# Server.net
KiCad netlist of a schematic drawn in EAGLE
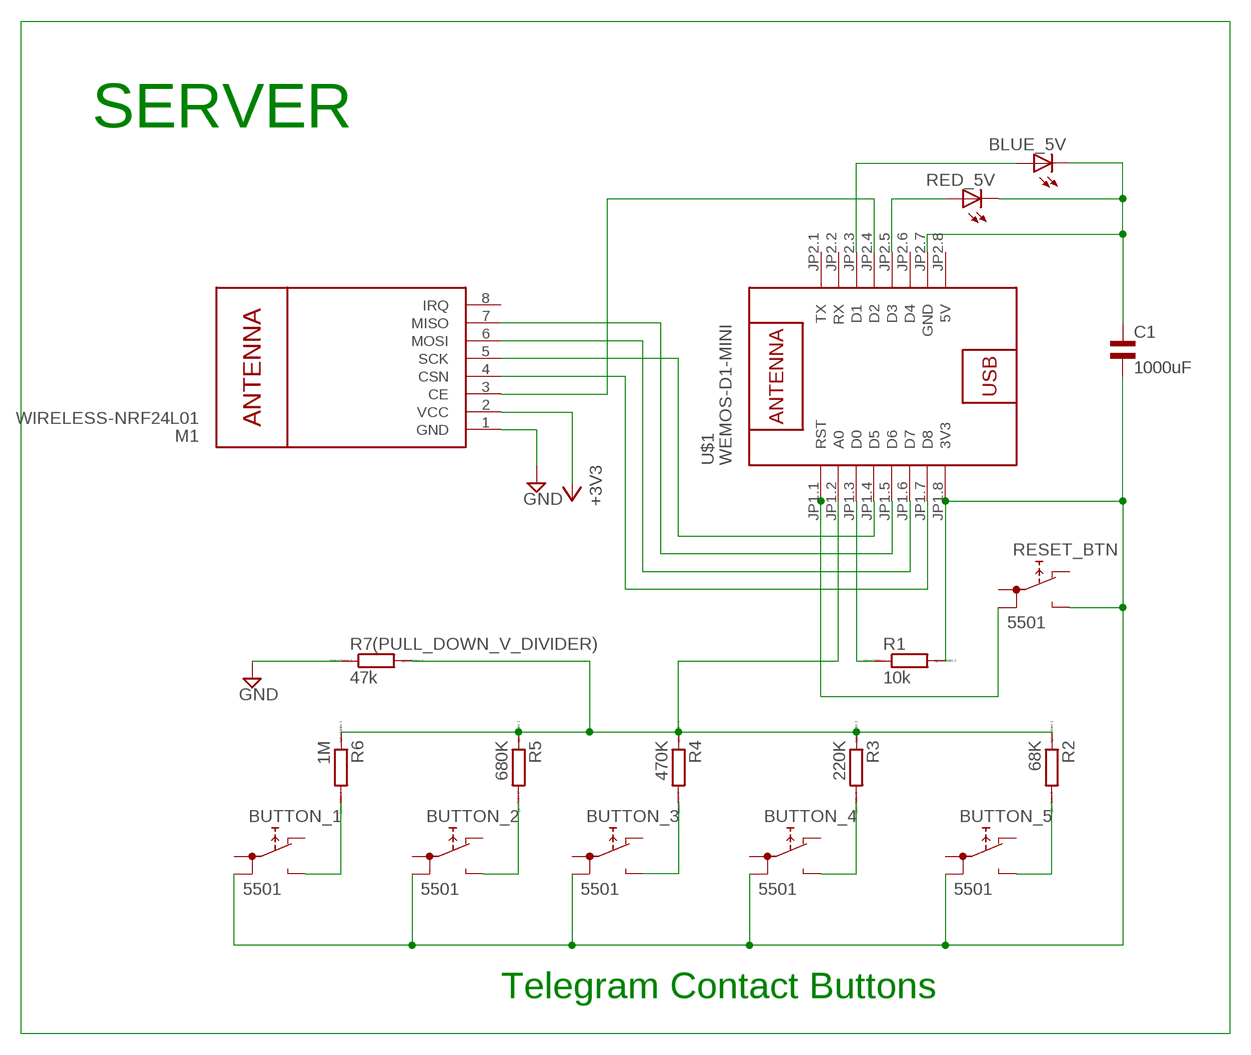
[diagram p0: schematic, sheet 1]

(export (version "E")
  (design (tool "Eeschema 10.0.6"))
  (components
    (comp (ref "BLUE_5V")
      (value "LED5MM")
      (footprint "eagle-import:LED5MM")
      (libsource (lib "eagle-import") (part "LED5MM"))
    )
    (comp (ref "BUTTON_1")
      (value "5501")
      (footprint "eagle-import:5501")
      (libsource (lib "eagle-import") (part "55?01"))
    )
    (comp (ref "BUTTON_2")
      (value "5501")
      (footprint "eagle-import:5501")
      (libsource (lib "eagle-import") (part "55?01"))
    )
    (comp (ref "BUTTON_3")
      (value "5501")
      (footprint "eagle-import:5501")
      (libsource (lib "eagle-import") (part "55?01"))
    )
    (comp (ref "BUTTON_4")
      (value "5501")
      (footprint "eagle-import:5501")
      (libsource (lib "eagle-import") (part "55?01"))
    )
    (comp (ref "BUTTON_5")
      (value "5501")
      (footprint "eagle-import:5501")
      (libsource (lib "eagle-import") (part "55?01"))
    )
    (comp (ref "C1")
      (value "1000uF")
      (footprint "eagle-import:EU35-12")
      (libsource (lib "eagle-import") (part "EL-BI35-12AXIAL"))
    )
    (comp (ref "M1")
      (value "WIRELESS-NRF24L01")
      (footprint "eagle-import:WIRELESS-NRF24L01")
      (libsource (lib "eagle-import") (part "WIRELESS-NRF24L01"))
    )
    (comp (ref "R1")
      (value "10k")
      (footprint "eagle-import:0207_10")
      (libsource (lib "eagle-import") (part "R0207/10"))
    )
    (comp (ref "R2")
      (value "68K")
      (footprint "eagle-import:0207_10")
      (libsource (lib "eagle-import") (part "R0207/10"))
    )
    (comp (ref "R3")
      (value "220K")
      (footprint "eagle-import:0207_10")
      (libsource (lib "eagle-import") (part "R0207/10"))
    )
    (comp (ref "R4")
      (value "470K")
      (footprint "eagle-import:0207_10")
      (libsource (lib "eagle-import") (part "R0207/10"))
    )
    (comp (ref "R5")
      (value "680K")
      (footprint "eagle-import:0207_10")
      (libsource (lib "eagle-import") (part "R0207/10"))
    )
    (comp (ref "R6")
      (value "1M")
      (footprint "eagle-import:0207_10")
      (libsource (lib "eagle-import") (part "R0207/10"))
    )
    (comp (ref "R7(PULL_DOWN_V_DIVIDER)")
      (value "47k")
      (footprint "eagle-import:0207_10")
      (libsource (lib "eagle-import") (part "R0207/10"))
    )
    (comp (ref "RED_5V")
      (value "LED5MM")
      (footprint "eagle-import:LED5MM")
      (libsource (lib "eagle-import") (part "LED5MM"))
    )
    (comp (ref "RESET_BTN")
      (value "5501")
      (footprint "eagle-import:5501")
      (libsource (lib "eagle-import") (part "55?01"))
    )
    (comp (ref "U$1")
      (value "WEMOS-D1-MINI")
      (footprint "eagle-import:WEMOS-D1-MINI")
      (libsource (lib "eagle-import") (part "WEMOS-D1-MINI"))
    )
  )
  (nets
    (net (code "1") (name "+3V3") (class "Default")
      (node (ref "M1") (pin "2") (pinfunction "VCC_2") (pintype "power_in"))
    )
    (net (code "2") (name "/5V") (class "Default")
      (node (ref "U$1") (pin "JP2.8") (pinfunction "5V_JP2.8") (pintype "power_in"))
    )
    (net (code "3") (name "GND") (class "Default")
      (node (ref "M1") (pin "1") (pinfunction "GND_1") (pintype "power_in"))
      (node (ref "R7(PULL_DOWN_V_DIVIDER)") (pin "1") (pinfunction "1_1") (pintype "passive"))
    )
    (net (code "4") (name "Net-(BLUE_5V-C)") (class "Default")
      (node (ref "BLUE_5V") (pin "K") (pinfunction "C_K") (pintype "passive"))
      (node (ref "C1") (pin "1") (pinfunction "1_1") (pintype "passive"))
      (node (ref "RED_5V") (pin "K") (pinfunction "C_K") (pintype "passive"))
      (node (ref "U$1") (pin "JP2.7") (pinfunction "GND_JP2.7") (pintype "power_in"))
    )
    (net (code "5") (name "Net-(BUTTON_1-PadNO)") (class "Default")
      (node (ref "BUTTON_1") (pin "NO") (pinfunction "NO_NO") (pintype "passive"))
      (node (ref "R6") (pin "2") (pinfunction "2_2") (pintype "passive"))
    )
    (net (code "6") (name "Net-(BUTTON_2-PadNO)") (class "Default")
      (node (ref "BUTTON_2") (pin "NO") (pinfunction "NO_NO") (pintype "passive"))
      (node (ref "R5") (pin "2") (pinfunction "2_2") (pintype "passive"))
    )
    (net (code "7") (name "Net-(BUTTON_3-PadNO)") (class "Default")
      (node (ref "BUTTON_3") (pin "NO") (pinfunction "NO_NO") (pintype "passive"))
      (node (ref "R4") (pin "2") (pinfunction "2_2") (pintype "passive"))
    )
    (net (code "8") (name "Net-(BUTTON_4-PadNO)") (class "Default")
      (node (ref "BUTTON_4") (pin "NO") (pinfunction "NO_NO") (pintype "passive"))
      (node (ref "R3") (pin "2") (pinfunction "2_2") (pintype "passive"))
    )
    (net (code "9") (name "Net-(BUTTON_5-PadNO)") (class "Default")
      (node (ref "BUTTON_5") (pin "NO") (pinfunction "NO_NO") (pintype "passive"))
      (node (ref "R2") (pin "2") (pinfunction "2_2") (pintype "passive"))
    )
    (net (code "10") (name "Net-(M1-CE)") (class "Default")
      (node (ref "M1") (pin "3") (pinfunction "CE_3") (pintype "bidirectional"))
      (node (ref "U$1") (pin "JP2.4") (pinfunction "D2_JP2.4") (pintype "bidirectional"))
    )
    (net (code "11") (name "Net-(M1-CSN)") (class "Default")
      (node (ref "M1") (pin "4") (pinfunction "CSN_4") (pintype "bidirectional"))
      (node (ref "U$1") (pin "JP1.7") (pinfunction "D8_JP1.7") (pintype "bidirectional"))
    )
    (net (code "12") (name "Net-(M1-MISO)") (class "Default")
      (node (ref "M1") (pin "7") (pinfunction "MISO_7") (pintype "bidirectional"))
      (node (ref "U$1") (pin "JP1.5") (pinfunction "D6_JP1.5") (pintype "bidirectional"))
    )
    (net (code "13") (name "Net-(M1-MOSI)") (class "Default")
      (node (ref "M1") (pin "6") (pinfunction "MOSI_6") (pintype "bidirectional"))
      (node (ref "U$1") (pin "JP1.6") (pinfunction "D7_JP1.6") (pintype "bidirectional"))
    )
    (net (code "14") (name "Net-(M1-SCK)") (class "Default")
      (node (ref "M1") (pin "5") (pinfunction "SCK_5") (pintype "bidirectional"))
      (node (ref "U$1") (pin "JP1.4") (pinfunction "D5_JP1.4") (pintype "bidirectional"))
    )
    (net (code "15") (name "Net-(U$1-3V3)") (class "Default")
      (node (ref "BUTTON_1") (pin "1B") (pinfunction "1B_1B") (pintype "passive"))
      (node (ref "BUTTON_2") (pin "1B") (pinfunction "1B_1B") (pintype "passive"))
      (node (ref "BUTTON_3") (pin "1B") (pinfunction "1B_1B") (pintype "passive"))
      (node (ref "BUTTON_4") (pin "1B") (pinfunction "1B_1B") (pintype "passive"))
      (node (ref "BUTTON_5") (pin "1B") (pinfunction "1B_1B") (pintype "passive"))
      (node (ref "C1") (pin "2") (pinfunction "2_2") (pintype "passive"))
      (node (ref "R1") (pin "2") (pinfunction "2_2") (pintype "passive"))
      (node (ref "RESET_BTN") (pin "NO") (pinfunction "NO_NO") (pintype "passive"))
      (node (ref "U$1") (pin "JP1.8") (pinfunction "3V3_JP1.8") (pintype "power_in"))
    )
    (net (code "16") (name "Net-(U$1-A0)") (class "Default")
      (node (ref "R2") (pin "1") (pinfunction "1_1") (pintype "passive"))
      (node (ref "R3") (pin "1") (pinfunction "1_1") (pintype "passive"))
      (node (ref "R4") (pin "1") (pinfunction "1_1") (pintype "passive"))
      (node (ref "R5") (pin "1") (pinfunction "1_1") (pintype "passive"))
      (node (ref "R6") (pin "1") (pinfunction "1_1") (pintype "passive"))
      (node (ref "R7(PULL_DOWN_V_DIVIDER)") (pin "2") (pinfunction "2_2") (pintype "passive"))
      (node (ref "U$1") (pin "JP1.2") (pinfunction "A0_JP1.2") (pintype "bidirectional"))
    )
    (net (code "17") (name "Net-(U$1-D0)") (class "Default")
      (node (ref "R1") (pin "1") (pinfunction "1_1") (pintype "passive"))
      (node (ref "U$1") (pin "JP1.3") (pinfunction "D0_JP1.3") (pintype "bidirectional"))
    )
    (net (code "18") (name "Net-(U$1-D1)") (class "Default")
      (node (ref "BLUE_5V") (pin "A") (pinfunction "A_A") (pintype "passive"))
      (node (ref "U$1") (pin "JP2.3") (pinfunction "D1_JP2.3") (pintype "bidirectional"))
    )
    (net (code "19") (name "Net-(U$1-D3)") (class "Default")
      (node (ref "RED_5V") (pin "A") (pinfunction "A_A") (pintype "passive"))
      (node (ref "U$1") (pin "JP2.5") (pinfunction "D3_JP2.5") (pintype "bidirectional"))
    )
    (net (code "20") (name "Net-(U$1-RST)") (class "Default")
      (node (ref "RESET_BTN") (pin "1B") (pinfunction "1B_1B") (pintype "passive"))
      (node (ref "U$1") (pin "JP1.1") (pinfunction "RST_JP1.1") (pintype "bidirectional"))
    )
    (net (code "21") (name "unconnected-(BUTTON_1-Pad1A)") (class "Default")
      (node (ref "BUTTON_1") (pin "1A") (pinfunction "1A_1A") (pintype "passive"))
    )
    (net (code "22") (name "unconnected-(BUTTON_1-PadNC)") (class "Default")
      (node (ref "BUTTON_1") (pin "NC") (pinfunction "NC_NC") (pintype "passive"))
    )
    (net (code "23") (name "unconnected-(BUTTON_2-Pad1A)") (class "Default")
      (node (ref "BUTTON_2") (pin "1A") (pinfunction "1A_1A") (pintype "passive"))
    )
    (net (code "24") (name "unconnected-(BUTTON_2-PadNC)") (class "Default")
      (node (ref "BUTTON_2") (pin "NC") (pinfunction "NC_NC") (pintype "passive"))
    )
    (net (code "25") (name "unconnected-(BUTTON_3-Pad1A)") (class "Default")
      (node (ref "BUTTON_3") (pin "1A") (pinfunction "1A_1A") (pintype "passive"))
    )
    (net (code "26") (name "unconnected-(BUTTON_3-PadNC)") (class "Default")
      (node (ref "BUTTON_3") (pin "NC") (pinfunction "NC_NC") (pintype "passive"))
    )
    (net (code "27") (name "unconnected-(BUTTON_4-Pad1A)") (class "Default")
      (node (ref "BUTTON_4") (pin "1A") (pinfunction "1A_1A") (pintype "passive"))
    )
    (net (code "28") (name "unconnected-(BUTTON_4-PadNC)") (class "Default")
      (node (ref "BUTTON_4") (pin "NC") (pinfunction "NC_NC") (pintype "passive"))
    )
    (net (code "29") (name "unconnected-(BUTTON_5-Pad1A)") (class "Default")
      (node (ref "BUTTON_5") (pin "1A") (pinfunction "1A_1A") (pintype "passive"))
    )
    (net (code "30") (name "unconnected-(BUTTON_5-PadNC)") (class "Default")
      (node (ref "BUTTON_5") (pin "NC") (pinfunction "NC_NC") (pintype "passive"))
    )
    (net (code "31") (name "unconnected-(M1-IRQ-Pad8)") (class "Default")
      (node (ref "M1") (pin "8") (pinfunction "IRQ_8") (pintype "bidirectional"))
    )
    (net (code "32") (name "unconnected-(RESET_BTN-Pad1A)") (class "Default")
      (node (ref "RESET_BTN") (pin "1A") (pinfunction "1A_1A") (pintype "passive"))
    )
    (net (code "33") (name "unconnected-(RESET_BTN-PadNC)") (class "Default")
      (node (ref "RESET_BTN") (pin "NC") (pinfunction "NC_NC") (pintype "passive"))
    )
    (net (code "34") (name "unconnected-(U$1-D4-PadJP2.6)") (class "Default")
      (node (ref "U$1") (pin "JP2.6") (pinfunction "D4_JP2.6") (pintype "bidirectional"))
    )
    (net (code "35") (name "unconnected-(U$1-RX-PadJP2.2)") (class "Default")
      (node (ref "U$1") (pin "JP2.2") (pinfunction "RX_JP2.2") (pintype "bidirectional"))
    )
    (net (code "36") (name "unconnected-(U$1-TX-PadJP2.1)") (class "Default")
      (node (ref "U$1") (pin "JP2.1") (pinfunction "TX_JP2.1") (pintype "bidirectional"))
    )
  )
)
